# Driver.net
KiCad netlist of a schematic drawn in Altium Designer
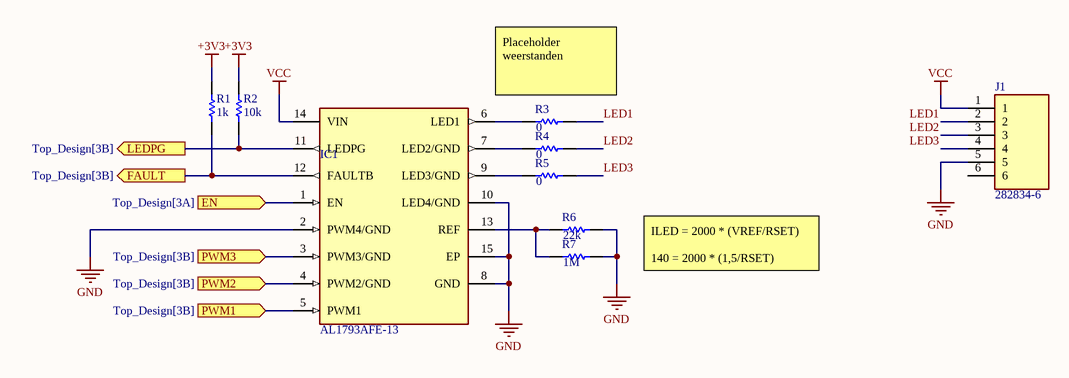
[diagram p0: Driver.SchDoc]

(export (version "E")
  (design (tool "Eeschema 10.0.6"))
  (components
    (comp (ref "IC1")
      (value "AL1793AFE-13")
      (footprint "SamacSys:AL1793AFE13")
      (description "Integrated Circuit")
      (fields (field (name "MOUSER PART NUMBER") "621-AL1793AFE-13"))
      (libsource (lib "SamacSys") (part "AL1793AFE-13"))
    )
    (comp (ref "J1")
      (value "282834-6")
      (footprint "SamacSys:2828346")
      (description "Connector")
      (fields (field (name "MOUSER PART NUMBER") "571-282834-6"))
      (libsource (lib "SamacSys") (part "282834-6"))
    )
    (comp (ref "R1")
      (value "1k")
      (footprint "RESC2013X70X40ML20T20")
      (description "Chip Resistor, 1 KOhm, +/- 1%, 0.125 W, -55 to 155 degC, 0805 (2013 Metric)")
      (fields (field (name "TOLERANCE") "1%") (field (name "POWER") "125mW"))
      (libsource (lib "Arne Van der Stede") (part "RES-2"))
    )
    (comp (ref "R2")
      (value "10k")
      (footprint "RESC2013X70X40ML20T20")
      (description "Chip Resistor, 10 KOhm, +/- 1%, 0.125 W, -55 to 155 degC, 0805 (2013 Metric)")
      (fields (field (name "TOLERANCE") "1%") (field (name "POWER") "125mW"))
      (libsource (lib "Arne Van der Stede") (part "RES-2"))
    )
    (comp (ref "R3")
      (value "0")
      (footprint "RESC2013X70X40ML20T20")
      (description "Chip Resistor, 0 Ohm, +/- 1%, 0.125 W, -55 to 155 degC, 0805 (2013 Metric)")
      (fields (field (name "TOLERANCE") "1%") (field (name "POWER") "125mW"))
      (libsource (lib "Arne Van der Stede") (part "RES-2"))
    )
    (comp (ref "R4")
      (value "0")
      (footprint "RESC2013X70X40ML20T20")
      (description "Chip Resistor, 0 Ohm, +/- 1%, 0.125 W, -55 to 155 degC, 0805 (2013 Metric)")
      (fields (field (name "TOLERANCE") "1%") (field (name "POWER") "125mW"))
      (libsource (lib "Arne Van der Stede") (part "RES-2"))
    )
    (comp (ref "R5")
      (value "0")
      (footprint "RESC2013X70X40ML20T20")
      (description "Chip Resistor, 0 Ohm, +/- 1%, 0.125 W, -55 to 155 degC, 0805 (2013 Metric)")
      (fields (field (name "TOLERANCE") "1%") (field (name "POWER") "125mW"))
      (libsource (lib "Arne Van der Stede") (part "RES-2"))
    )
    (comp (ref "R6")
      (value "22k")
      (footprint "RESC2013X70X40ML20T20")
      (description "Chip Resistor, 22 KOhm, +/- 1%, 0.125 W, -55 to 155 degC, 0805 (2013 Metric)")
      (fields (field (name "TOLERANCE") "1%") (field (name "POWER") "125mW"))
      (libsource (lib "Arne Van der Stede") (part "RES-2"))
    )
    (comp (ref "R7")
      (value "1M")
      (footprint "RESC2013X70X40ML20T20")
      (description "Chip Resistor, 1 MOhm, +/- 1%, 0.125 W, -55 to 155 degC, 0805 (2013 Metric)")
      (fields (field (name "TOLERANCE") "1%") (field (name "POWER") "125mW"))
      (libsource (lib "Arne Van der Stede") (part "RES-2"))
    )
  )
  (nets
    (net (code "1") (name "+3V3") (class "Default")
      (node (ref "R1") (pin "2") (pinfunction "2_2") (pintype "passive"))
      (node (ref "R2") (pin "2") (pinfunction "2_2") (pintype "passive"))
    )
    (net (code "2") (name "/EN") (class "Default")
      (node (ref "IC1") (pin "1") (pinfunction "EN_1") (pintype "input"))
    )
    (net (code "3") (name "/FAULT") (class "Default")
      (node (ref "IC1") (pin "12") (pinfunction "FAULTB_12") (pintype "output"))
      (node (ref "R1") (pin "1") (pinfunction "1_1") (pintype "passive"))
    )
    (net (code "4") (name "/LED1") (class "Default")
      (node (ref "J1") (pin "2") (pinfunction "2_2") (pintype "passive"))
      (node (ref "R3") (pin "2") (pinfunction "2_2") (pintype "passive"))
    )
    (net (code "5") (name "/LED2") (class "Default")
      (node (ref "J1") (pin "3") (pinfunction "3_3") (pintype "passive"))
      (node (ref "R4") (pin "2") (pinfunction "2_2") (pintype "passive"))
    )
    (net (code "6") (name "/LED3") (class "Default")
      (node (ref "J1") (pin "4") (pinfunction "4_4") (pintype "passive"))
      (node (ref "R5") (pin "2") (pinfunction "2_2") (pintype "passive"))
    )
    (net (code "7") (name "/LEDPG") (class "Default")
      (node (ref "IC1") (pin "11") (pinfunction "LEDPG_11") (pintype "output"))
      (node (ref "R2") (pin "1") (pinfunction "1_1") (pintype "passive"))
    )
    (net (code "8") (name "/PWM1") (class "Default")
      (node (ref "IC1") (pin "5") (pinfunction "PWM1_5") (pintype "input"))
    )
    (net (code "9") (name "/PWM2") (class "Default")
      (node (ref "IC1") (pin "4") (pinfunction "PWM2/GND_4") (pintype "input"))
    )
    (net (code "10") (name "/PWM3") (class "Default")
      (node (ref "IC1") (pin "3") (pinfunction "PWM3/GND_3") (pintype "input"))
    )
    (net (code "11") (name "GND") (class "Default")
      (node (ref "IC1") (pin "10") (pinfunction "LED4/GND_10") (pintype "passive"))
      (node (ref "IC1") (pin "15") (pinfunction "EP_15") (pintype "passive"))
      (node (ref "IC1") (pin "2") (pinfunction "PWM4/GND_2") (pintype "input"))
      (node (ref "IC1") (pin "8") (pinfunction "GND_8") (pintype "passive"))
      (node (ref "J1") (pin "5") (pinfunction "5_5") (pintype "passive"))
      (node (ref "R6") (pin "2") (pinfunction "2_2") (pintype "passive"))
      (node (ref "R7") (pin "2") (pinfunction "2_2") (pintype "passive"))
    )
    (net (code "12") (name "Net-(IC1-LED1)") (class "Default")
      (node (ref "IC1") (pin "6") (pinfunction "LED1_6") (pintype "output"))
      (node (ref "R3") (pin "1") (pinfunction "1_1") (pintype "passive"))
    )
    (net (code "13") (name "Net-(IC1-LED2{slash}GND)") (class "Default")
      (node (ref "IC1") (pin "7") (pinfunction "LED2/GND_7") (pintype "output"))
      (node (ref "R4") (pin "1") (pinfunction "1_1") (pintype "passive"))
    )
    (net (code "14") (name "Net-(IC1-LED3{slash}GND)") (class "Default")
      (node (ref "IC1") (pin "9") (pinfunction "LED3/GND_9") (pintype "output"))
      (node (ref "R5") (pin "1") (pinfunction "1_1") (pintype "passive"))
    )
    (net (code "15") (name "Net-(IC1-REF)") (class "Default")
      (node (ref "IC1") (pin "13") (pinfunction "REF_13") (pintype "passive"))
      (node (ref "R6") (pin "1") (pinfunction "1_1") (pintype "passive"))
      (node (ref "R7") (pin "1") (pinfunction "1_1") (pintype "passive"))
    )
    (net (code "16") (name "VCC") (class "Default")
      (node (ref "IC1") (pin "14") (pinfunction "VIN_14") (pintype "power_in"))
      (node (ref "J1") (pin "1") (pinfunction "1_1") (pintype "passive"))
    )
    (net (code "17") (name "unconnected-(J1-Pad6)") (class "Default")
      (node (ref "J1") (pin "6") (pinfunction "6_6") (pintype "passive"))
    )
  )
)
